# TOP_VOLTAGE.net
KiCad netlist of a schematic drawn in Altium Designer
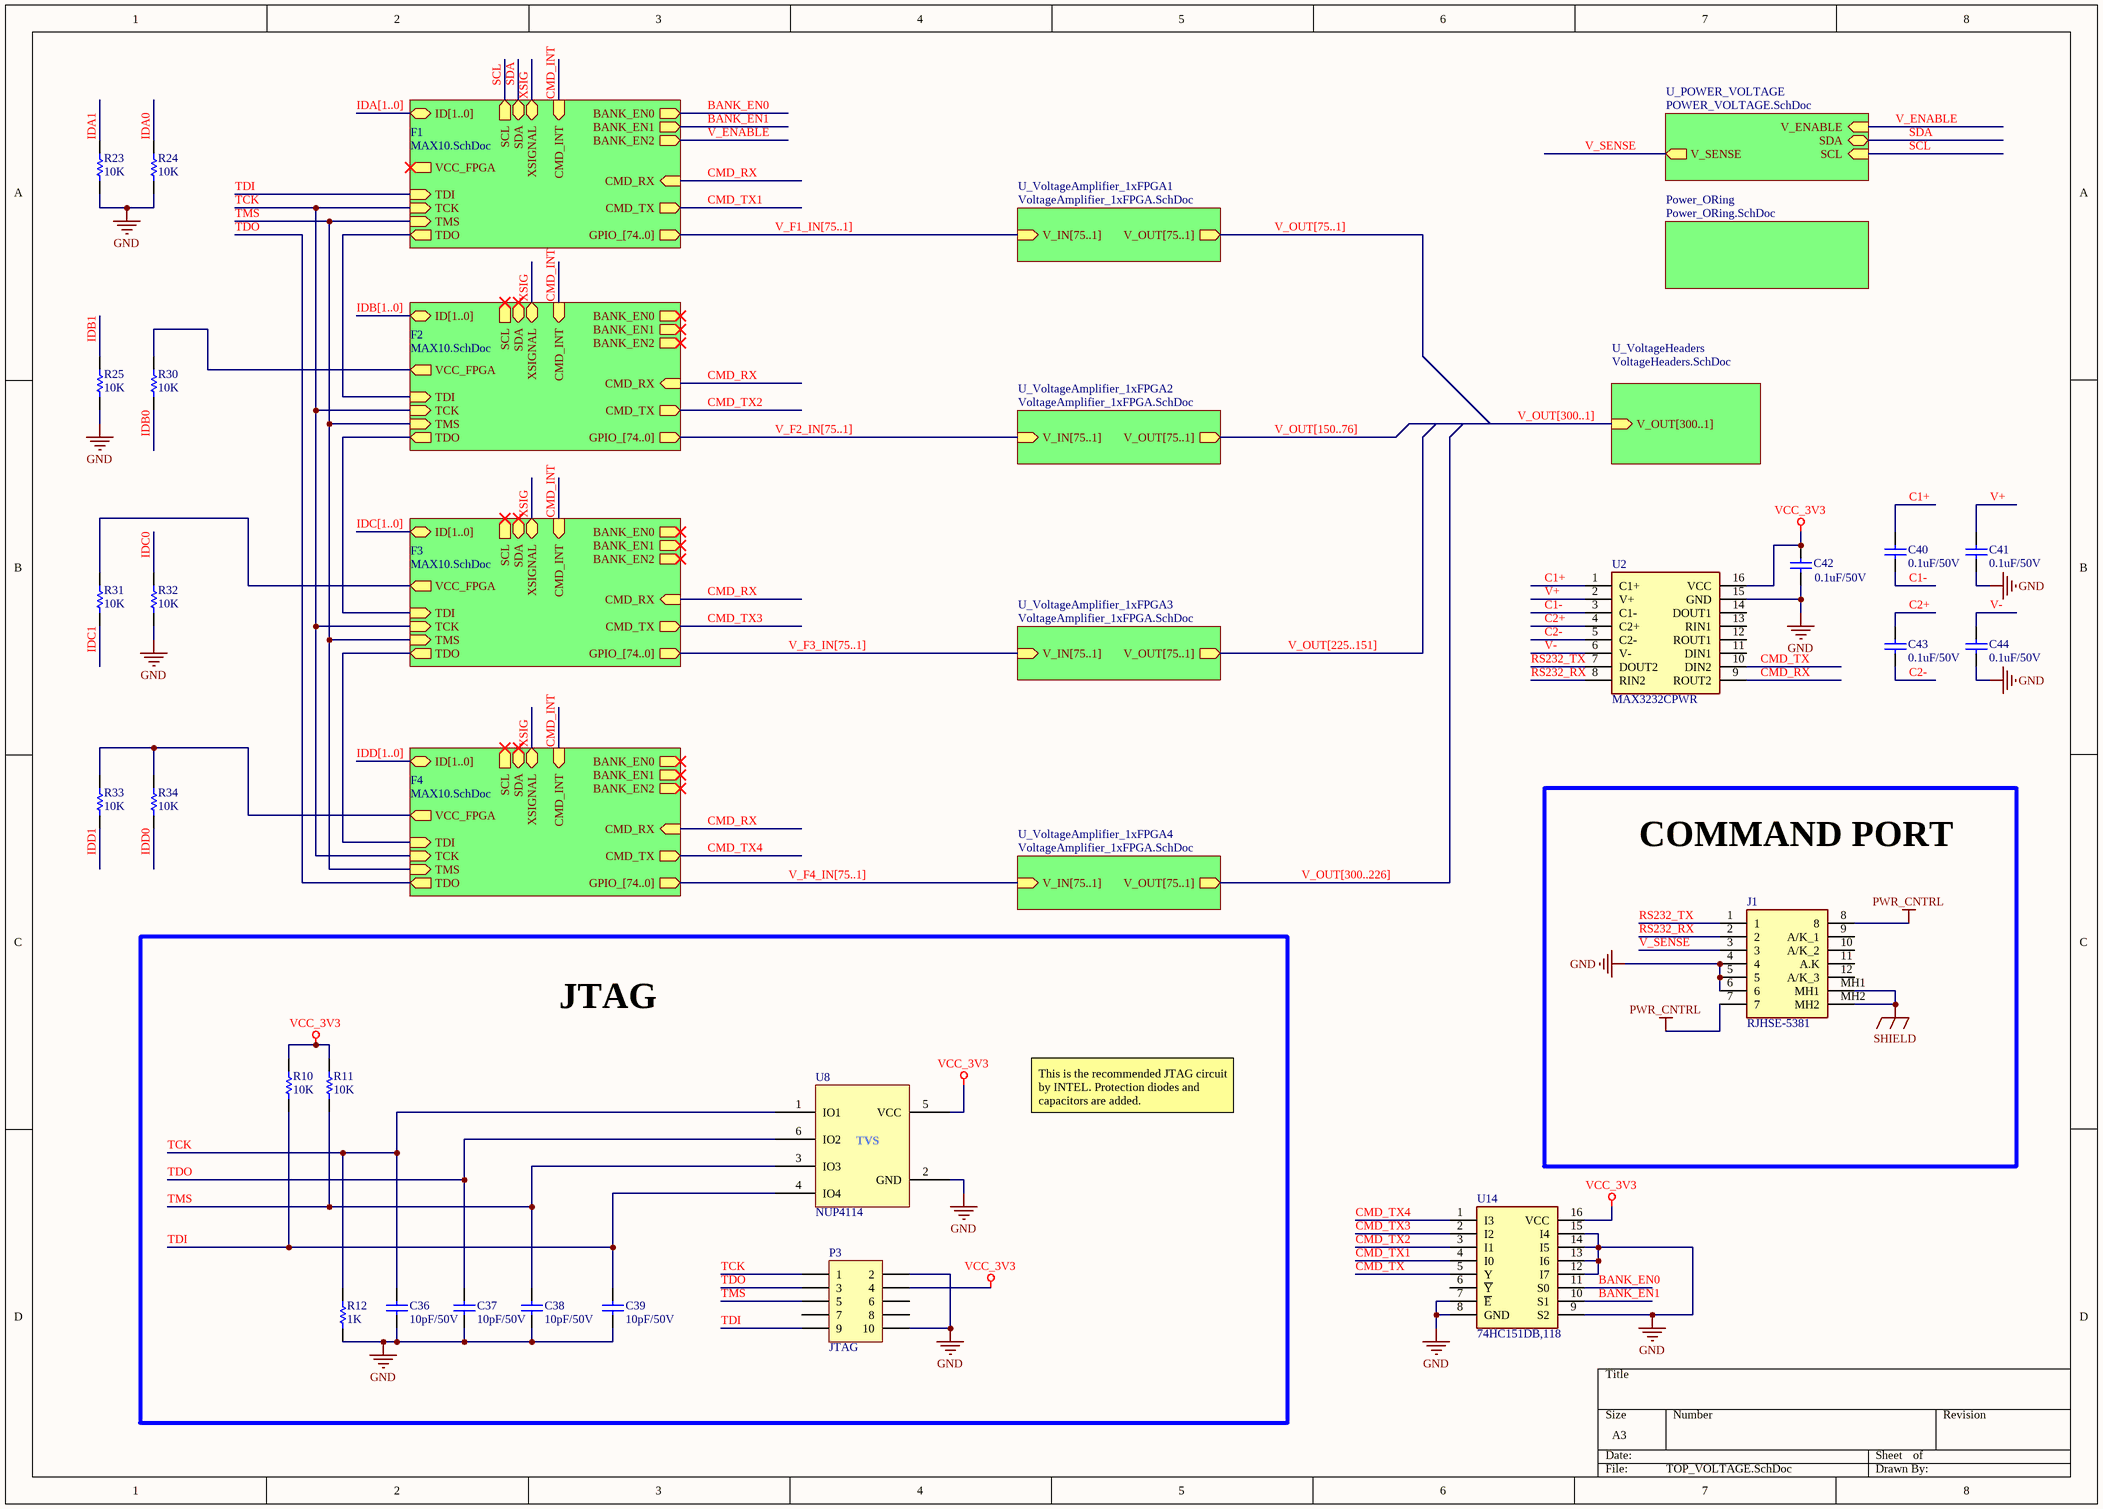
[diagram p0: TOP_VOLTAGE.SchDoc]

(export (version "E")
  (design (tool "Eeschema 10.0.6"))
  (components
    (comp (ref "C36")
      (value "10pF/50V")
      (footprint "0603C")
      (description "Multilayer Ceramic Capacitors MLCC - SMD/SMT 50V 10pF 0603 C0G 5% AEC-Q200")
      (fields (field (name "MFR") "KEMET") (field (name "MFR PART NO") "C0603C100J5GACAUTO"))
      (libsource (lib "Miscellaneous Devices") (part "Cap"))
    )
    (comp (ref "C37")
      (value "10pF/50V")
      (footprint "0603C")
      (description "Multilayer Ceramic Capacitors MLCC - SMD/SMT 50V 10pF 0603 C0G 5% AEC-Q200")
      (fields (field (name "MFR") "KEMET") (field (name "MFR PART NO") "C0603C100J5GACAUTO"))
      (libsource (lib "Miscellaneous Devices") (part "Cap"))
    )
    (comp (ref "C38")
      (value "10pF/50V")
      (footprint "0603C")
      (description "Multilayer Ceramic Capacitors MLCC - SMD/SMT 50V 10pF 0603 C0G 5% AEC-Q200")
      (fields (field (name "MFR") "KEMET") (field (name "MFR PART NO") "C0603C100J5GACAUTO"))
      (libsource (lib "Miscellaneous Devices") (part "Cap"))
    )
    (comp (ref "C39")
      (value "10pF/50V")
      (footprint "0603C")
      (description "Multilayer Ceramic Capacitors MLCC - SMD/SMT 50V 10pF 0603 C0G 5% AEC-Q200")
      (fields (field (name "MFR") "KEMET") (field (name "MFR PART NO") "C0603C100J5GACAUTO"))
      (libsource (lib "Miscellaneous Devices") (part "Cap"))
    )
    (comp (ref "C40")
      (value "0.1uF/50V")
      (footprint "0603C")
      (description "Multilayer Ceramic Capacitors MLCC - SMD/SMT 50V 0.1uF 0603 X7R 20%")
      (fields (field (name "MFR") "KEMET") (field (name "MFR PART NO") "C0603C104M5RACTU"))
      (libsource (lib "Miscellaneous Devices") (part "Cap"))
    )
    (comp (ref "C41")
      (value "0.1uF/50V")
      (footprint "0603C")
      (description "Multilayer Ceramic Capacitors MLCC - SMD/SMT 50V 0.1uF 0603 X7R 20%")
      (fields (field (name "MFR") "KEMET") (field (name "MFR PART NO") "C0603C104M5RACTU"))
      (libsource (lib "Miscellaneous Devices") (part "Cap"))
    )
    (comp (ref "C42")
      (value "0.1uF/50V")
      (footprint "0603C")
      (description "Multilayer Ceramic Capacitors MLCC - SMD/SMT 50V 0.1uF 0603 X7R 20%")
      (fields (field (name "MFR") "KEMET") (field (name "MFR PART NO") "C0603C104M5RACTU"))
      (libsource (lib "Miscellaneous Devices") (part "Cap"))
    )
    (comp (ref "C43")
      (value "0.1uF/50V")
      (footprint "0603C")
      (description "Multilayer Ceramic Capacitors MLCC - SMD/SMT 50V 0.1uF 0603 X7R 20%")
      (fields (field (name "MFR") "KEMET") (field (name "MFR PART NO") "C0603C104M5RACTU"))
      (libsource (lib "Miscellaneous Devices") (part "Cap"))
    )
    (comp (ref "C44")
      (value "0.1uF/50V")
      (footprint "0603C")
      (description "Multilayer Ceramic Capacitors MLCC - SMD/SMT 50V 0.1uF 0603 X7R 20%")
      (fields (field (name "MFR") "KEMET") (field (name "MFR PART NO") "C0603C104M5RACTU"))
      (libsource (lib "Miscellaneous Devices") (part "Cap"))
    )
    (comp (ref "J1")
      (value "RJHSE-5381")
      (footprint "ProjCLib:RJHSE5381")
      (description "Modular Connectors / Ethernet Connectors R/A RJ45 SHEILDED 8 CONT Y/G LEDS")
      (fields
        (field (name "MFR") "Amphenol Commercial Products")
        (field (name "STOCKIEST PART NO") "523-RJHSE-5381")
      )
      (libsource (lib "*") (part "RJHSE-5381"))
    )
    (comp (ref "P3")
      (value "JTAG")
      (footprint "HDR2X5")
      (description "Header, 5-Pin, Dual row")
      (libsource (lib "Miscellaneous Connectors") (part "Header 5X2"))
    )
    (comp (ref "R10")
      (value "10K")
      (footprint "0603R")
      (description "Thick Film Resistors - SMD 0603 10Kohms 1% Anti-Sulfur AEC-Q200")
      (fields (field (name "MFR") "ROHM Semiconductor") (field (name "MFR PART NO") "SFR03EZPF1002"))
      (libsource (lib "Miscellaneous Devices") (part "Res1"))
    )
    (comp (ref "R11")
      (value "10K")
      (footprint "0603R")
      (description "Thick Film Resistors - SMD 0603 10Kohms 1% Anti-Sulfur AEC-Q200")
      (fields (field (name "MFR") "ROHM Semiconductor") (field (name "MFR PART NO") "SFR03EZPF1002"))
      (libsource (lib "Miscellaneous Devices") (part "Res1"))
    )
    (comp (ref "R12")
      (value "1K")
      (footprint "0603R")
      (description "Resistor")
      (fields (field (name "MFR") "Vishay / Dale") (field (name "MFR PART NO") "CRCW06031K00FKEAC"))
      (libsource (lib "Miscellaneous Devices") (part "Res1"))
    )
    (comp (ref "R23")
      (value "10K")
      (footprint "0603R")
      (description "Thick Film Resistors - SMD 0603 10Kohms 1% Anti-Sulfur AEC-Q200")
      (fields (field (name "MFR") "ROHM Semiconductor") (field (name "MFR PART NO") "SFR03EZPF1002"))
      (libsource (lib "Miscellaneous Devices") (part "Res1"))
    )
    (comp (ref "R24")
      (value "10K")
      (footprint "0603R")
      (description "Thick Film Resistors - SMD 0603 10Kohms 1% Anti-Sulfur AEC-Q200")
      (fields (field (name "MFR") "ROHM Semiconductor") (field (name "MFR PART NO") "SFR03EZPF1002"))
      (libsource (lib "Miscellaneous Devices") (part "Res1"))
    )
    (comp (ref "R25")
      (value "10K")
      (footprint "0603R")
      (description "Thick Film Resistors - SMD 0603 10Kohms 1% Anti-Sulfur AEC-Q200")
      (fields (field (name "MFR") "ROHM Semiconductor") (field (name "MFR PART NO") "SFR03EZPF1002"))
      (libsource (lib "Miscellaneous Devices") (part "Res1"))
    )
    (comp (ref "R30")
      (value "10K")
      (footprint "0603R")
      (description "Thick Film Resistors - SMD 0603 10Kohms 1% Anti-Sulfur AEC-Q200")
      (fields (field (name "MFR") "ROHM Semiconductor") (field (name "MFR PART NO") "SFR03EZPF1002"))
      (libsource (lib "Miscellaneous Devices") (part "Res1"))
    )
    (comp (ref "R31")
      (value "10K")
      (footprint "0603R")
      (description "Thick Film Resistors - SMD 0603 10Kohms 1% Anti-Sulfur AEC-Q200")
      (fields (field (name "MFR") "ROHM Semiconductor") (field (name "MFR PART NO") "SFR03EZPF1002"))
      (libsource (lib "Miscellaneous Devices") (part "Res1"))
    )
    (comp (ref "R32")
      (value "10K")
      (footprint "0603R")
      (description "Thick Film Resistors - SMD 0603 10Kohms 1% Anti-Sulfur AEC-Q200")
      (fields (field (name "MFR") "ROHM Semiconductor") (field (name "MFR PART NO") "SFR03EZPF1002"))
      (libsource (lib "Miscellaneous Devices") (part "Res1"))
    )
    (comp (ref "R33")
      (value "10K")
      (footprint "0603R")
      (description "Thick Film Resistors - SMD 0603 10Kohms 1% Anti-Sulfur AEC-Q200")
      (fields (field (name "MFR") "ROHM Semiconductor") (field (name "MFR PART NO") "SFR03EZPF1002"))
      (libsource (lib "Miscellaneous Devices") (part "Res1"))
    )
    (comp (ref "R34")
      (value "10K")
      (footprint "0603R")
      (description "Thick Film Resistors - SMD 0603 10Kohms 1% Anti-Sulfur AEC-Q200")
      (fields (field (name "MFR") "ROHM Semiconductor") (field (name "MFR PART NO") "SFR03EZPF1002"))
      (libsource (lib "Miscellaneous Devices") (part "Res1"))
    )
    (comp (ref "U2")
      (value "MAX3232CPWR")
      (footprint "MAX3232CPWR")
      (description "RS-232 Interface IC 3-5.5V Mult-Ch RS232")
      (fields (field (name "MFR") "Texas Instruments") (field (name "STOCKIEST PART NO") "595-MAX3232CPWR"))
      (libsource (lib "*") (part "MAX3232CPWR"))
    )
    (comp (ref "U8")
      (value "NUP4114")
      (footprint "NUP4114HMR6T1G")
      (description "ESD Suppressors / TVS Diodes LOW CAP TVS ARRAY 5.5V")
      (fields (field (name "MFR") "ON SEMI") (field (name "MFR PART NO") "NUP4114HMR6T1G"))
      (libsource (lib "Schlib1") (part "NUP4114"))
    )
    (comp (ref "U14")
      (value "74HC151DB,118")
      (footprint "74HC151DB,118")
      (description "Encoders, Decoders, Multiplexers & Demultiplexers 8-INPUT MULTIPLEXER")
      (fields (field (name "MFR") "NEXPERIA") (field (name "STOCKIEST PART NO") "771-HC151DB118"))
      (libsource (lib "*") (part "74HC151DB,118"))
    )
  )
  (nets
    (net (code "601") (name "/BANK_EN0") (class "Default")
      (node (ref "U14") (pin "11") (pinfunction "S0_11") (pintype "passive"))
    )
    (net (code "605") (name "/BANK_EN1") (class "Default")
      (node (ref "U14") (pin "10") (pinfunction "S1_10") (pintype "passive"))
    )
    (net (code "612") (name "/C1+") (class "Default")
      (node (ref "C40") (pin "2") (pinfunction "2_2") (pintype "passive"))
      (node (ref "U2") (pin "1") (pinfunction "C1+_1") (pintype "passive"))
    )
    (net (code "613") (name "/C1-") (class "Default")
      (node (ref "C40") (pin "1") (pinfunction "1_1") (pintype "passive"))
      (node (ref "U2") (pin "3") (pinfunction "C1-_3") (pintype "passive"))
    )
    (net (code "614") (name "/C2+") (class "Default")
      (node (ref "C43") (pin "2") (pinfunction "2_2") (pintype "passive"))
      (node (ref "U2") (pin "4") (pinfunction "C2+_4") (pintype "passive"))
    )
    (net (code "615") (name "/C2-") (class "Default")
      (node (ref "C43") (pin "1") (pinfunction "1_1") (pintype "passive"))
      (node (ref "U2") (pin "5") (pinfunction "C2-_5") (pintype "passive"))
    )
    (net (code "617") (name "/CMD_RX") (class "Default")
      (node (ref "U2") (pin "9") (pinfunction "ROUT2_9") (pintype "passive"))
    )
    (net (code "618") (name "/CMD_TX") (class "Default")
      (node (ref "U14") (pin "5") (pinfunction "Y_5") (pintype "passive"))
      (node (ref "U2") (pin "10") (pinfunction "DIN2_10") (pintype "passive"))
    )
    (net (code "619") (name "/CMD_TX1") (class "Default")
      (node (ref "U14") (pin "4") (pinfunction "I0_4") (pintype "passive"))
    )
    (net (code "620") (name "/CMD_TX2") (class "Default")
      (node (ref "U14") (pin "3") (pinfunction "I1_3") (pintype "passive"))
    )
    (net (code "621") (name "/CMD_TX3") (class "Default")
      (node (ref "U14") (pin "2") (pinfunction "I2_2") (pintype "passive"))
    )
    (net (code "622") (name "/CMD_TX4") (class "Default")
      (node (ref "U14") (pin "1") (pinfunction "I3_1") (pintype "passive"))
    )
    (net (code "623") (name "/IDA0") (class "Default")
      (node (ref "R24") (pin "1") (pinfunction "1_1") (pintype "passive"))
    )
    (net (code "624") (name "/IDA1") (class "Default")
      (node (ref "R23") (pin "1") (pinfunction "1_1") (pintype "passive"))
    )
    (net (code "626") (name "/IDB0") (class "Default")
      (node (ref "R30") (pin "2") (pinfunction "2_2") (pintype "passive"))
    )
    (net (code "627") (name "/IDB1") (class "Default")
      (node (ref "R25") (pin "1") (pinfunction "1_1") (pintype "passive"))
    )
    (net (code "629") (name "/IDC0") (class "Default")
      (node (ref "R32") (pin "1") (pinfunction "1_1") (pintype "passive"))
    )
    (net (code "630") (name "/IDC1") (class "Default")
      (node (ref "R31") (pin "2") (pinfunction "2_2") (pintype "passive"))
    )
    (net (code "632") (name "/IDD0") (class "Default")
      (node (ref "R34") (pin "2") (pinfunction "2_2") (pintype "passive"))
    )
    (net (code "633") (name "/IDD1") (class "Default")
      (node (ref "R33") (pin "2") (pinfunction "2_2") (pintype "passive"))
    )
    (net (code "635") (name "/RS232_RX") (class "Default")
      (node (ref "J1") (pin "2") (pinfunction "2_2") (pintype "passive"))
      (node (ref "U2") (pin "8") (pinfunction "RIN2_8") (pintype "passive"))
    )
    (net (code "636") (name "/RS232_TX") (class "Default")
      (node (ref "J1") (pin "1") (pinfunction "1_1") (pintype "passive"))
      (node (ref "U2") (pin "7") (pinfunction "DOUT2_7") (pintype "passive"))
    )
    (net (code "645") (name "/TCK") (class "Default")
      (node (ref "C36") (pin "2") (pinfunction "2_2") (pintype "passive"))
      (node (ref "P3") (pin "1") (pinfunction "1_1") (pintype "passive"))
      (node (ref "R12") (pin "2") (pinfunction "2_2") (pintype "passive"))
      (node (ref "U8") (pin "1") (pinfunction "IO1_1") (pintype "passive"))
    )
    (net (code "646") (name "/TDI") (class "Default")
      (node (ref "C39") (pin "2") (pinfunction "2_2") (pintype "passive"))
      (node (ref "P3") (pin "9") (pinfunction "9_9") (pintype "passive"))
      (node (ref "R10") (pin "2") (pinfunction "2_2") (pintype "passive"))
      (node (ref "U8") (pin "4") (pinfunction "IO4_4") (pintype "passive"))
    )
    (net (code "647") (name "/TDO") (class "Default")
      (node (ref "C37") (pin "2") (pinfunction "2_2") (pintype "passive"))
      (node (ref "P3") (pin "3") (pinfunction "3_3") (pintype "passive"))
      (node (ref "U8") (pin "6") (pinfunction "IO2_6") (pintype "passive"))
    )
    (net (code "651") (name "/TMS") (class "Default")
      (node (ref "C38") (pin "2") (pinfunction "2_2") (pintype "passive"))
      (node (ref "P3") (pin "5") (pinfunction "5_5") (pintype "passive"))
      (node (ref "R11") (pin "2") (pinfunction "2_2") (pintype "passive"))
      (node (ref "U8") (pin "3") (pinfunction "IO3_3") (pintype "passive"))
    )
    (net (code "652") (name "/V+") (class "Default")
      (node (ref "C41") (pin "2") (pinfunction "2_2") (pintype "passive"))
      (node (ref "U2") (pin "2") (pinfunction "V+_2") (pintype "passive"))
    )
    (net (code "653") (name "/V-") (class "Default")
      (node (ref "C44") (pin "2") (pinfunction "2_2") (pintype "passive"))
      (node (ref "U2") (pin "6") (pinfunction "V-_6") (pintype "passive"))
    )
    (net (code "655") (name "/VCC_FPGA_1") (class "Default")
      (node (ref "R33") (pin "1") (pinfunction "1_1") (pintype "passive"))
      (node (ref "R34") (pin "1") (pinfunction "1_1") (pintype "passive"))
    )
    (net (code "656") (name "/VCC_FPGA_2") (class "Default")
      (node (ref "R30") (pin "1") (pinfunction "1_1") (pintype "passive"))
    )
    (net (code "657") (name "/VCC_FPGA_3") (class "Default")
      (node (ref "R31") (pin "1") (pinfunction "1_1") (pintype "passive"))
    )
    (net (code "668") (name "/V_SENSE") (class "Default")
      (node (ref "J1") (pin "3") (pinfunction "3_3") (pintype "passive"))
    )
    (net (code "670") (name "GND") (class "Default")
      (node (ref "C36") (pin "1") (pinfunction "1_1") (pintype "passive"))
      (node (ref "C37") (pin "1") (pinfunction "1_1") (pintype "passive"))
      (node (ref "C38") (pin "1") (pinfunction "1_1") (pintype "passive"))
      (node (ref "C39") (pin "1") (pinfunction "1_1") (pintype "passive"))
      (node (ref "C41") (pin "1") (pinfunction "1_1") (pintype "passive"))
      (node (ref "C42") (pin "1") (pinfunction "1_1") (pintype "passive"))
      (node (ref "C44") (pin "1") (pinfunction "1_1") (pintype "passive"))
      (node (ref "J1") (pin "4") (pinfunction "4_4") (pintype "passive"))
      (node (ref "J1") (pin "5") (pinfunction "5_5") (pintype "passive"))
      (node (ref "J1") (pin "6") (pinfunction "6_6") (pintype "passive"))
      (node (ref "P3") (pin "10") (pinfunction "10_10") (pintype "passive"))
      (node (ref "P3") (pin "2") (pinfunction "2_2") (pintype "passive"))
      (node (ref "R12") (pin "1") (pinfunction "1_1") (pintype "passive"))
      (node (ref "R23") (pin "2") (pinfunction "2_2") (pintype "passive"))
      (node (ref "R24") (pin "2") (pinfunction "2_2") (pintype "passive"))
      (node (ref "R25") (pin "2") (pinfunction "2_2") (pintype "passive"))
      (node (ref "R32") (pin "2") (pinfunction "2_2") (pintype "passive"))
      (node (ref "U14") (pin "12") (pinfunction "I7_12") (pintype "passive"))
      (node (ref "U14") (pin "13") (pinfunction "I6_13") (pintype "passive"))
      (node (ref "U14") (pin "14") (pinfunction "I5_14") (pintype "passive"))
      (node (ref "U14") (pin "15") (pinfunction "I4_15") (pintype "passive"))
      (node (ref "U14") (pin "7") (pinfunction "~{E}_7") (pintype "passive"))
      (node (ref "U14") (pin "8") (pinfunction "GND_8") (pintype "passive"))
      (node (ref "U14") (pin "9") (pinfunction "S2_9") (pintype "passive"))
      (node (ref "U2") (pin "15") (pinfunction "GND_15") (pintype "passive"))
      (node (ref "U8") (pin "2") (pinfunction "GND_2") (pintype "passive"))
    )
    (net (code "671") (name "PWR_CNTRL") (class "Default")
      (node (ref "J1") (pin "7") (pinfunction "7_7") (pintype "passive"))
      (node (ref "J1") (pin "8") (pinfunction "8_8") (pintype "passive"))
    )
    (net (code "672") (name "SHIELD") (class "Default")
      (node (ref "J1") (pin "MH1") (pinfunction "MH1_MH1") (pintype "passive"))
      (node (ref "J1") (pin "MH2") (pinfunction "MH2_MH2") (pintype "passive"))
    )
    (net (code "673") (name "VCC_3V3") (class "Default")
      (node (ref "C42") (pin "2") (pinfunction "2_2") (pintype "passive"))
      (node (ref "P3") (pin "4") (pinfunction "4_4") (pintype "passive"))
      (node (ref "R10") (pin "1") (pinfunction "1_1") (pintype "passive"))
      (node (ref "R11") (pin "1") (pinfunction "1_1") (pintype "passive"))
      (node (ref "U14") (pin "16") (pinfunction "VCC_16") (pintype "passive"))
      (node (ref "U2") (pin "16") (pinfunction "VCC_16") (pintype "passive"))
      (node (ref "U8") (pin "5") (pinfunction "VCC_5") (pintype "passive"))
    )
    (net (code "674") (name "unconnected-(J1-A.K-Pad11)") (class "Default")
      (node (ref "J1") (pin "11") (pinfunction "A.K_11") (pintype "passive"))
    )
    (net (code "675") (name "unconnected-(J1-A{slash}K_1-Pad9)") (class "Default")
      (node (ref "J1") (pin "9") (pinfunction "A/K_1_9") (pintype "passive"))
    )
    (net (code "676") (name "unconnected-(J1-A{slash}K_2-Pad10)") (class "Default")
      (node (ref "J1") (pin "10") (pinfunction "A/K_2_10") (pintype "passive"))
    )
    (net (code "677") (name "unconnected-(J1-A{slash}K_3-Pad12)") (class "Default")
      (node (ref "J1") (pin "12") (pinfunction "A/K_3_12") (pintype "passive"))
    )
    (net (code "678") (name "unconnected-(P3-Pad6)") (class "Default")
      (node (ref "P3") (pin "6") (pinfunction "6_6") (pintype "passive"))
    )
    (net (code "679") (name "unconnected-(P3-Pad7)") (class "Default")
      (node (ref "P3") (pin "7") (pinfunction "7_7") (pintype "passive"))
    )
    (net (code "680") (name "unconnected-(P3-Pad8)") (class "Default")
      (node (ref "P3") (pin "8") (pinfunction "8_8") (pintype "passive"))
    )
    (net (code "681") (name "unconnected-(U2-DIN1-Pad11)") (class "Default")
      (node (ref "U2") (pin "11") (pinfunction "DIN1_11") (pintype "passive"))
    )
    (net (code "682") (name "unconnected-(U2-DOUT1-Pad14)") (class "Default")
      (node (ref "U2") (pin "14") (pinfunction "DOUT1_14") (pintype "passive"))
    )
    (net (code "683") (name "unconnected-(U2-RIN1-Pad13)") (class "Default")
      (node (ref "U2") (pin "13") (pinfunction "RIN1_13") (pintype "passive"))
    )
    (net (code "684") (name "unconnected-(U2-ROUT1-Pad12)") (class "Default")
      (node (ref "U2") (pin "12") (pinfunction "ROUT1_12") (pintype "passive"))
    )
    (net (code "685") (name "unconnected-(U14-~{Y}-Pad6)") (class "Default")
      (node (ref "U14") (pin "6") (pinfunction "~{Y}_6") (pintype "passive"))
    )
  )
)
